# 15_SOLEDNOID.net
KiCad netlist of a schematic drawn in Altium Designer
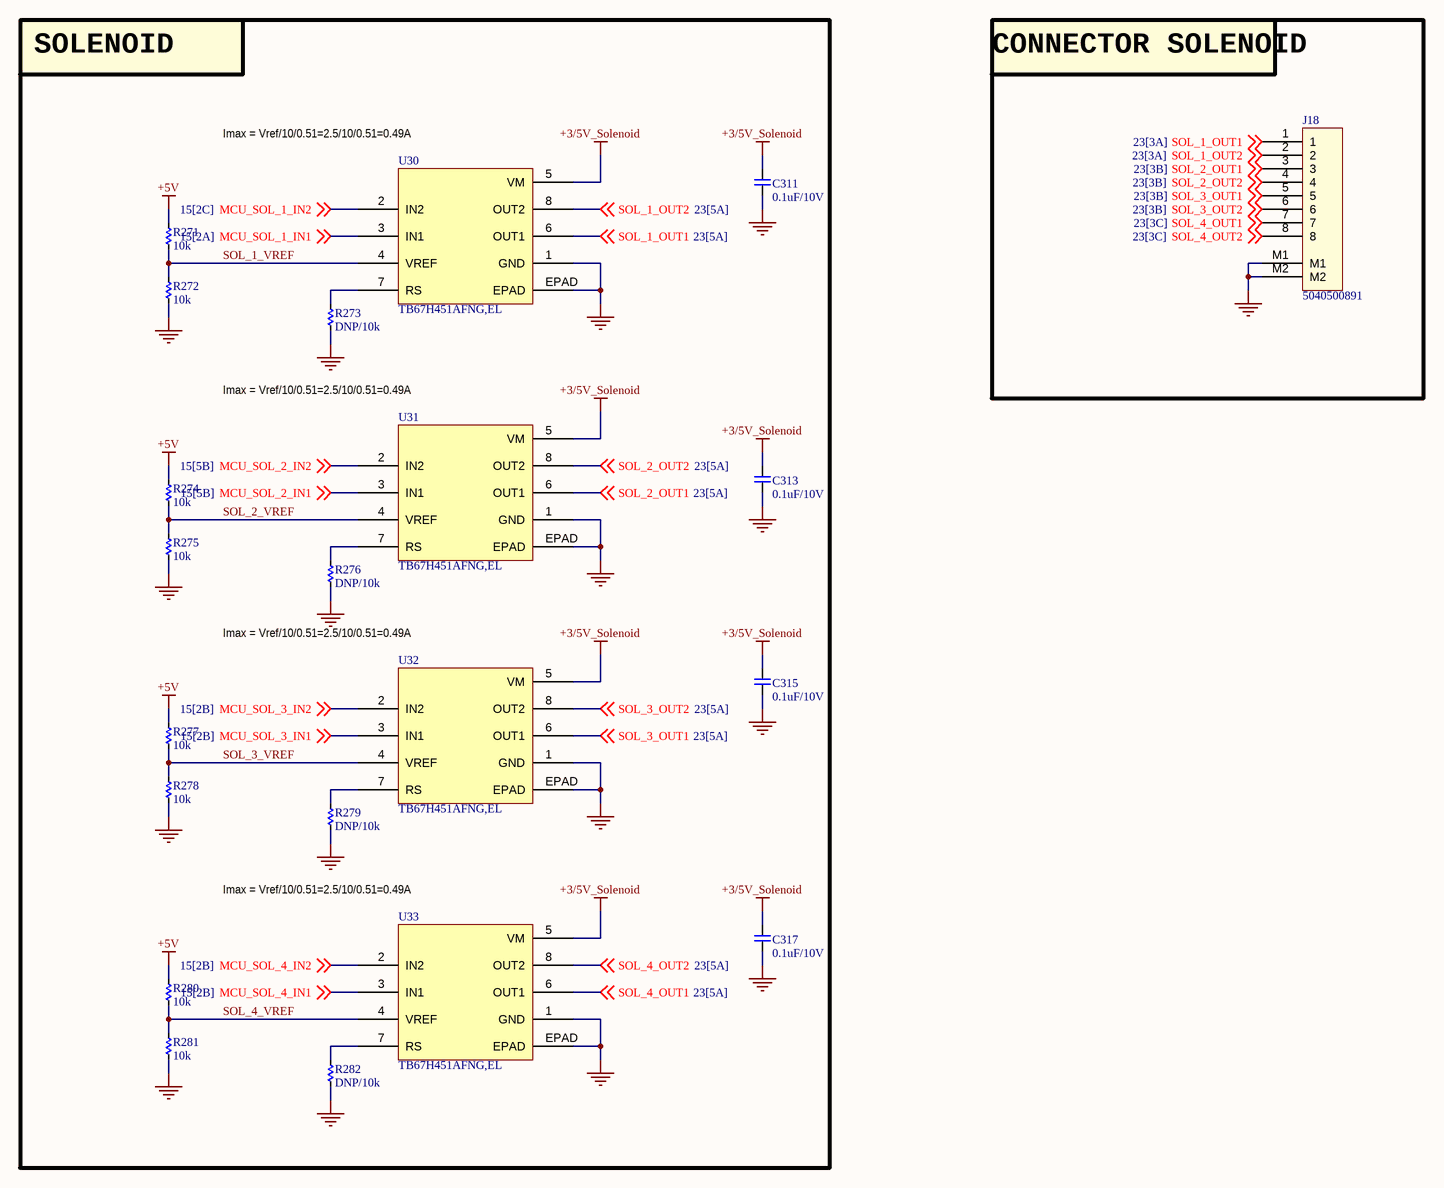
[diagram p0: 15_SOLEDNOID.SchDoc]

(export (version "E")
  (design (tool "Eeschema 10.0.6"))
  (components
    (comp (ref "C311")
      (value "0.1uF/10V")
      (footprint "CAP_C_1005X60")
      (description "CAP CHIP")
      (libsource (lib "LABLIB") (part "_CAP_C_2"))
    )
    (comp (ref "C313")
      (value "0.1uF/10V")
      (footprint "CAP_C_1005X60")
      (description "CAP CHIP")
      (libsource (lib "LABLIB") (part "_CAP_C_2"))
    )
    (comp (ref "C315")
      (value "0.1uF/10V")
      (footprint "CAP_C_1005X60")
      (description "CAP CHIP")
      (libsource (lib "LABLIB") (part "_CAP_C_2"))
    )
    (comp (ref "C317")
      (value "0.1uF/10V")
      (footprint "CAP_C_1005X60")
      (description "CAP CHIP")
      (libsource (lib "LABLIB") (part "_CAP_C_2"))
    )
    (comp (ref "J18")
      (value "5040500891")
      (footprint "MOLEX_5040500891")
      (libsource (lib "LABLIB") (part "Header 8x1_2M"))
    )
    (comp (ref "R271")
      (value "10k")
      (footprint "RES_C_1005X40")
      (description "RES")
      (libsource (lib "LABLIB") (part "_RES_B_2"))
    )
    (comp (ref "R272")
      (value "10k")
      (footprint "RES_C_1005X40")
      (description "RES")
      (libsource (lib "LABLIB") (part "_RES_B_2"))
    )
    (comp (ref "R273")
      (value "DNP/10k")
      (footprint "RES_C_1005X40")
      (description "RES")
      (libsource (lib "LABLIB") (part "_RES_B_2"))
    )
    (comp (ref "R274")
      (value "10k")
      (footprint "RES_C_1005X40")
      (description "RES")
      (libsource (lib "LABLIB") (part "_RES_B_2"))
    )
    (comp (ref "R275")
      (value "10k")
      (footprint "RES_C_1005X40")
      (description "RES")
      (libsource (lib "LABLIB") (part "_RES_B_2"))
    )
    (comp (ref "R276")
      (value "DNP/10k")
      (footprint "RES_C_1005X40")
      (description "RES")
      (libsource (lib "LABLIB") (part "_RES_B_2"))
    )
    (comp (ref "R277")
      (value "10k")
      (footprint "RES_C_1005X40")
      (description "RES")
      (libsource (lib "LABLIB") (part "_RES_B_2"))
    )
    (comp (ref "R278")
      (value "10k")
      (footprint "RES_C_1005X40")
      (description "RES")
      (libsource (lib "LABLIB") (part "_RES_B_2"))
    )
    (comp (ref "R279")
      (value "DNP/10k")
      (footprint "RES_C_1005X40")
      (description "RES")
      (libsource (lib "LABLIB") (part "_RES_B_2"))
    )
    (comp (ref "R280")
      (value "10k")
      (footprint "RES_C_1005X40")
      (description "RES")
      (libsource (lib "LABLIB") (part "_RES_B_2"))
    )
    (comp (ref "R281")
      (value "10k")
      (footprint "RES_C_1005X40")
      (description "RES")
      (libsource (lib "LABLIB") (part "_RES_B_2"))
    )
    (comp (ref "R282")
      (value "DNP/10k")
      (footprint "RES_C_1005X40")
      (description "RES")
      (libsource (lib "LABLIB") (part "_RES_B_2"))
    )
    (comp (ref "U30")
      (value "TB67H451AFNG,EL")
      (footprint "SOIC127P602X173-8N_EPAD")
      (description "BRUSHED MOTOR DRIVER IC, 50V, 3.")
      (libsource (lib "LABLIB") (part "IC_H_bridge_TB67H451AFNG,EL"))
    )
    (comp (ref "U31")
      (value "TB67H451AFNG,EL")
      (footprint "SOIC127P602X173-8N_EPAD")
      (description "BRUSHED MOTOR DRIVER IC, 50V, 3.")
      (libsource (lib "LABLIB") (part "IC_H_bridge_TB67H451AFNG,EL"))
    )
    (comp (ref "U32")
      (value "TB67H451AFNG,EL")
      (footprint "SOIC127P602X173-8N_EPAD")
      (description "BRUSHED MOTOR DRIVER IC, 50V, 3.")
      (libsource (lib "LABLIB") (part "IC_H_bridge_TB67H451AFNG,EL"))
    )
    (comp (ref "U33")
      (value "TB67H451AFNG,EL")
      (footprint "SOIC127P602X173-8N_EPAD")
      (description "BRUSHED MOTOR DRIVER IC, 50V, 3.")
      (libsource (lib "LABLIB") (part "IC_H_bridge_TB67H451AFNG,EL"))
    )
  )
  (nets
    (net (code "1") (name "+3{slash}5V_Solenoid") (class "Default")
      (node (ref "C311") (pin "2") (pinfunction "2_2") (pintype "passive"))
      (node (ref "C313") (pin "2") (pinfunction "2_2") (pintype "passive"))
      (node (ref "C315") (pin "2") (pinfunction "2_2") (pintype "passive"))
      (node (ref "C317") (pin "2") (pinfunction "2_2") (pintype "passive"))
      (node (ref "U30") (pin "5") (pinfunction "VM_5") (pintype "passive"))
      (node (ref "U31") (pin "5") (pinfunction "VM_5") (pintype "passive"))
      (node (ref "U32") (pin "5") (pinfunction "VM_5") (pintype "passive"))
      (node (ref "U33") (pin "5") (pinfunction "VM_5") (pintype "passive"))
    )
    (net (code "2") (name "+5V") (class "Default")
      (node (ref "R271") (pin "1") (pinfunction "1_1") (pintype "passive"))
      (node (ref "R274") (pin "1") (pinfunction "1_1") (pintype "passive"))
      (node (ref "R277") (pin "1") (pinfunction "1_1") (pintype "passive"))
      (node (ref "R280") (pin "1") (pinfunction "1_1") (pintype "passive"))
    )
    (net (code "3") (name "/SOL_1_VREF") (class "Default")
      (node (ref "R271") (pin "2") (pinfunction "2_2") (pintype "passive"))
      (node (ref "R272") (pin "1") (pinfunction "1_1") (pintype "passive"))
      (node (ref "U30") (pin "4") (pinfunction "VREF_4") (pintype "passive"))
    )
    (net (code "4") (name "/SOL_2_VREF") (class "Default")
      (node (ref "R274") (pin "2") (pinfunction "2_2") (pintype "passive"))
      (node (ref "R275") (pin "1") (pinfunction "1_1") (pintype "passive"))
      (node (ref "U31") (pin "4") (pinfunction "VREF_4") (pintype "passive"))
    )
    (net (code "5") (name "/SOL_3_VREF") (class "Default")
      (node (ref "R277") (pin "2") (pinfunction "2_2") (pintype "passive"))
      (node (ref "R278") (pin "1") (pinfunction "1_1") (pintype "passive"))
      (node (ref "U32") (pin "4") (pinfunction "VREF_4") (pintype "passive"))
    )
    (net (code "6") (name "/SOL_4_VREF") (class "Default")
      (node (ref "R280") (pin "2") (pinfunction "2_2") (pintype "passive"))
      (node (ref "R281") (pin "1") (pinfunction "1_1") (pintype "passive"))
      (node (ref "U33") (pin "4") (pinfunction "VREF_4") (pintype "passive"))
    )
    (net (code "7") (name "GND") (class "Default")
      (node (ref "C311") (pin "1") (pinfunction "1_1") (pintype "passive"))
      (node (ref "C313") (pin "1") (pinfunction "1_1") (pintype "passive"))
      (node (ref "C315") (pin "1") (pinfunction "1_1") (pintype "passive"))
      (node (ref "C317") (pin "1") (pinfunction "1_1") (pintype "passive"))
      (node (ref "J18") (pin "M1") (pinfunction "M1_M1") (pintype "passive"))
      (node (ref "J18") (pin "M2") (pinfunction "M2_M2") (pintype "passive"))
      (node (ref "R272") (pin "2") (pinfunction "2_2") (pintype "passive"))
      (node (ref "R273") (pin "2") (pinfunction "2_2") (pintype "passive"))
      (node (ref "R275") (pin "2") (pinfunction "2_2") (pintype "passive"))
      (node (ref "R276") (pin "2") (pinfunction "2_2") (pintype "passive"))
      (node (ref "R278") (pin "2") (pinfunction "2_2") (pintype "passive"))
      (node (ref "R279") (pin "2") (pinfunction "2_2") (pintype "passive"))
      (node (ref "R281") (pin "2") (pinfunction "2_2") (pintype "passive"))
      (node (ref "R282") (pin "2") (pinfunction "2_2") (pintype "passive"))
      (node (ref "U30") (pin "1") (pinfunction "GND_1") (pintype "passive"))
      (node (ref "U30") (pin "EPAD") (pinfunction "EPAD_EPAD") (pintype "passive"))
      (node (ref "U31") (pin "1") (pinfunction "GND_1") (pintype "passive"))
      (node (ref "U31") (pin "EPAD") (pinfunction "EPAD_EPAD") (pintype "passive"))
      (node (ref "U32") (pin "1") (pinfunction "GND_1") (pintype "passive"))
      (node (ref "U32") (pin "EPAD") (pinfunction "EPAD_EPAD") (pintype "passive"))
      (node (ref "U33") (pin "1") (pinfunction "GND_1") (pintype "passive"))
      (node (ref "U33") (pin "EPAD") (pinfunction "EPAD_EPAD") (pintype "passive"))
    )
    (net (code "8") (name "MCU_SOL_1_IN1") (class "Default")
      (node (ref "U30") (pin "3") (pinfunction "IN1_3") (pintype "passive"))
    )
    (net (code "9") (name "MCU_SOL_1_IN2") (class "Default")
      (node (ref "U30") (pin "2") (pinfunction "IN2_2") (pintype "passive"))
    )
    (net (code "10") (name "MCU_SOL_2_IN1") (class "Default")
      (node (ref "U31") (pin "3") (pinfunction "IN1_3") (pintype "passive"))
    )
    (net (code "11") (name "MCU_SOL_2_IN2") (class "Default")
      (node (ref "U31") (pin "2") (pinfunction "IN2_2") (pintype "passive"))
    )
    (net (code "12") (name "MCU_SOL_3_IN1") (class "Default")
      (node (ref "U32") (pin "3") (pinfunction "IN1_3") (pintype "passive"))
    )
    (net (code "13") (name "MCU_SOL_3_IN2") (class "Default")
      (node (ref "U32") (pin "2") (pinfunction "IN2_2") (pintype "passive"))
    )
    (net (code "14") (name "MCU_SOL_4_IN1") (class "Default")
      (node (ref "U33") (pin "3") (pinfunction "IN1_3") (pintype "passive"))
    )
    (net (code "15") (name "MCU_SOL_4_IN2") (class "Default")
      (node (ref "U33") (pin "2") (pinfunction "IN2_2") (pintype "passive"))
    )
    (net (code "16") (name "Net-(U30-RS)") (class "Default")
      (node (ref "R273") (pin "1") (pinfunction "1_1") (pintype "passive"))
      (node (ref "U30") (pin "7") (pinfunction "RS_7") (pintype "passive"))
    )
    (net (code "17") (name "Net-(U31-RS)") (class "Default")
      (node (ref "R276") (pin "1") (pinfunction "1_1") (pintype "passive"))
      (node (ref "U31") (pin "7") (pinfunction "RS_7") (pintype "passive"))
    )
    (net (code "18") (name "Net-(U32-RS)") (class "Default")
      (node (ref "R279") (pin "1") (pinfunction "1_1") (pintype "passive"))
      (node (ref "U32") (pin "7") (pinfunction "RS_7") (pintype "passive"))
    )
    (net (code "19") (name "Net-(U33-RS)") (class "Default")
      (node (ref "R282") (pin "1") (pinfunction "1_1") (pintype "passive"))
      (node (ref "U33") (pin "7") (pinfunction "RS_7") (pintype "passive"))
    )
    (net (code "20") (name "SOL_1_OUT1") (class "Default")
      (node (ref "J18") (pin "1") (pinfunction "1_1") (pintype "passive"))
      (node (ref "U30") (pin "6") (pinfunction "OUT1_6") (pintype "passive"))
    )
    (net (code "21") (name "SOL_1_OUT2") (class "Default")
      (node (ref "J18") (pin "2") (pinfunction "2_2") (pintype "passive"))
      (node (ref "U30") (pin "8") (pinfunction "OUT2_8") (pintype "passive"))
    )
    (net (code "22") (name "SOL_2_OUT1") (class "Default")
      (node (ref "J18") (pin "3") (pinfunction "3_3") (pintype "passive"))
      (node (ref "U31") (pin "6") (pinfunction "OUT1_6") (pintype "passive"))
    )
    (net (code "23") (name "SOL_2_OUT2") (class "Default")
      (node (ref "J18") (pin "4") (pinfunction "4_4") (pintype "passive"))
      (node (ref "U31") (pin "8") (pinfunction "OUT2_8") (pintype "passive"))
    )
    (net (code "24") (name "SOL_3_OUT1") (class "Default")
      (node (ref "J18") (pin "5") (pinfunction "5_5") (pintype "passive"))
      (node (ref "U32") (pin "6") (pinfunction "OUT1_6") (pintype "passive"))
    )
    (net (code "25") (name "SOL_3_OUT2") (class "Default")
      (node (ref "J18") (pin "6") (pinfunction "6_6") (pintype "passive"))
      (node (ref "U32") (pin "8") (pinfunction "OUT2_8") (pintype "passive"))
    )
    (net (code "26") (name "SOL_4_OUT1") (class "Default")
      (node (ref "J18") (pin "7") (pinfunction "7_7") (pintype "passive"))
      (node (ref "U33") (pin "6") (pinfunction "OUT1_6") (pintype "passive"))
    )
    (net (code "27") (name "SOL_4_OUT2") (class "Default")
      (node (ref "J18") (pin "8") (pinfunction "8_8") (pintype "passive"))
      (node (ref "U33") (pin "8") (pinfunction "OUT2_8") (pintype "passive"))
    )
  )
)
